# arpie2_display.net
KiCad netlist of a schematic drawn in EAGLE
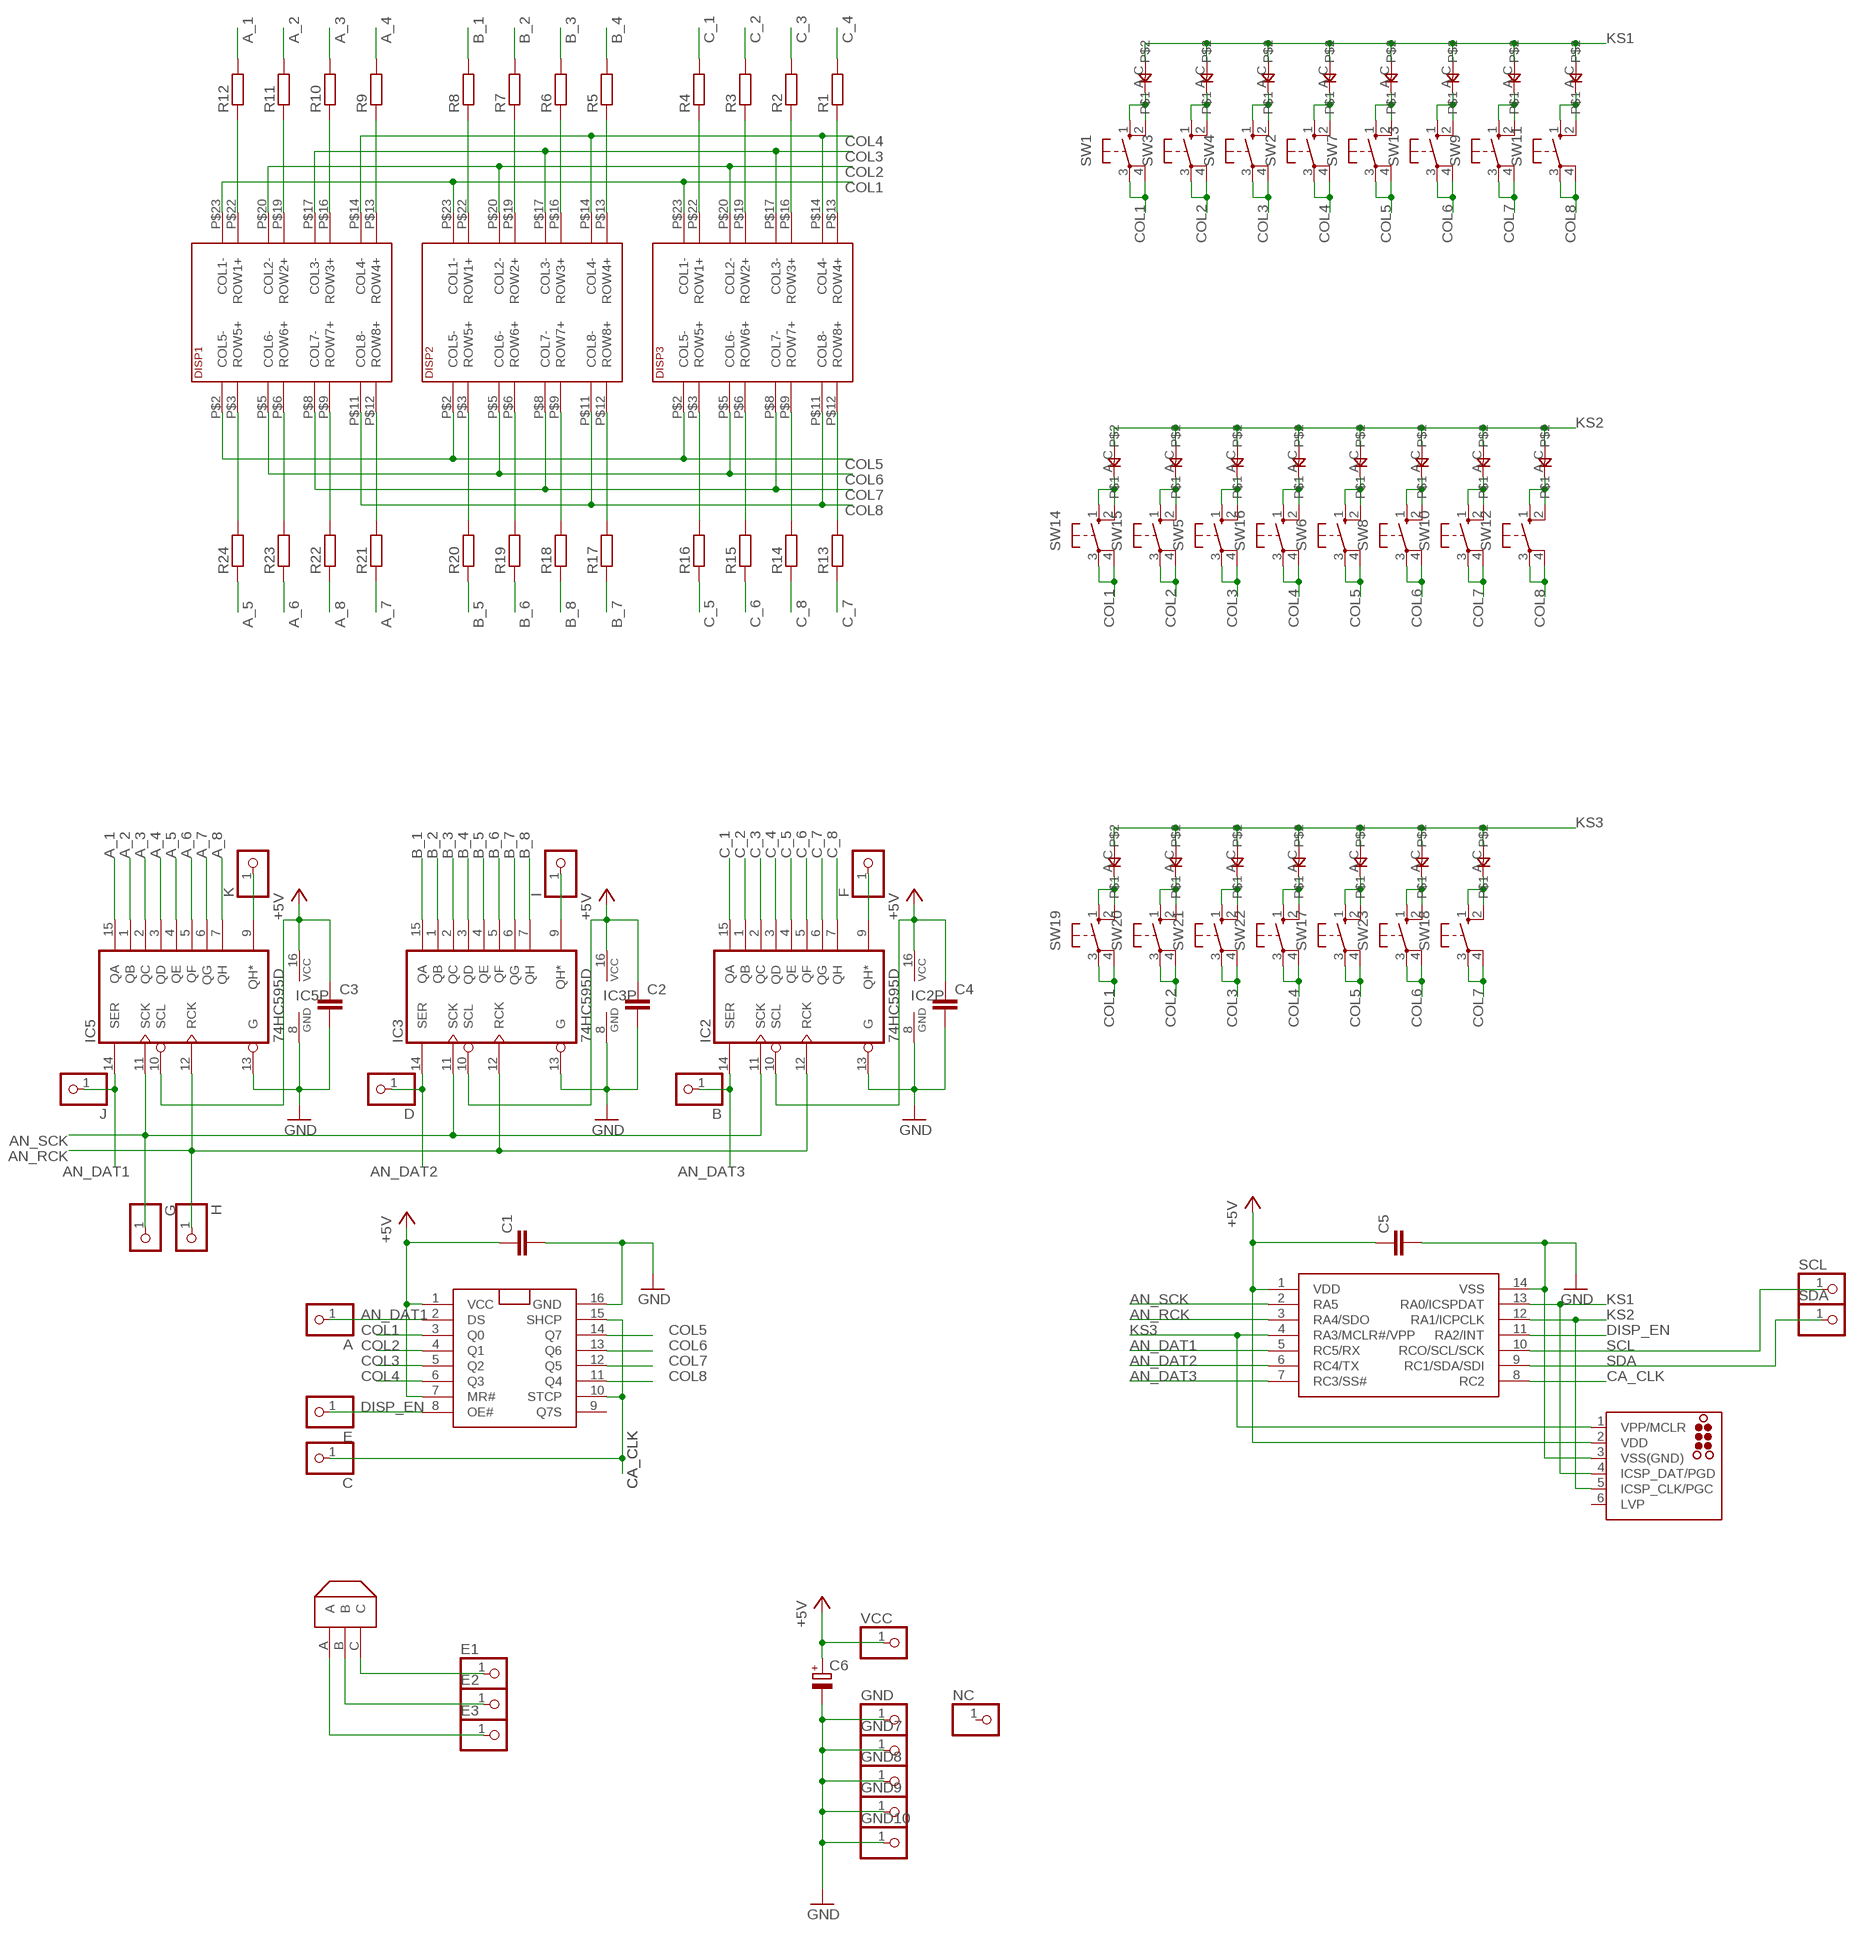
[diagram p0: schematic, sheet 1]

(export (version "E")
  (design (tool "Eeschema 10.0.6"))
  (components
    (comp (ref "A")
      (value "PINHD-1X1")
      (footprint "eagle-import:1X01")
      (libsource (lib "eagle-import") (part "PINHD-1X1"))
    )
    (comp (ref "B")
      (value "PINHD-1X1")
      (footprint "eagle-import:1X01")
      (libsource (lib "eagle-import") (part "PINHD-1X1"))
    )
    (comp (ref "C")
      (value "PINHD-1X1")
      (footprint "eagle-import:1X01")
      (libsource (lib "eagle-import") (part "PINHD-1X1"))
    )
    (comp (ref "C1")
      (value "C-EUC0805")
      (footprint "eagle-import:C0805")
      (libsource (lib "eagle-import") (part "C-EUC0805"))
    )
    (comp (ref "C2")
      (value "C-EUC0805")
      (footprint "eagle-import:C0805")
      (libsource (lib "eagle-import") (part "C-EUC0805"))
    )
    (comp (ref "C3")
      (value "C-EUC0805")
      (footprint "eagle-import:C0805")
      (libsource (lib "eagle-import") (part "C-EUC0805"))
    )
    (comp (ref "C4")
      (value "C-EUC0805")
      (footprint "eagle-import:C0805")
      (libsource (lib "eagle-import") (part "C-EUC0805"))
    )
    (comp (ref "C5")
      (value "C-EUC0805")
      (footprint "eagle-import:C0805")
      (libsource (lib "eagle-import") (part "C-EUC0805"))
    )
    (comp (ref "C6")
      (value "CPOL-EUE2,5-6E")
      (footprint "eagle-import:E2,5-6E")
      (libsource (lib "eagle-import") (part "CPOL-EUE2,5-6E"))
    )
    (comp (ref "D")
      (value "PINHD-1X1")
      (footprint "eagle-import:1X01")
      (libsource (lib "eagle-import") (part "PINHD-1X1"))
    )
    (comp (ref "DISP1")
      (value "1388BBMATRIX")
      (footprint "eagle-import:1388LEDMATRIX")
      (libsource (lib "eagle-import") (part "1388BBMATRIX"))
    )
    (comp (ref "DISP2")
      (value "1388BBMATRIX")
      (footprint "eagle-import:1388LEDMATRIX")
      (libsource (lib "eagle-import") (part "1388BBMATRIX"))
    )
    (comp (ref "DISP3")
      (value "1388BBMATRIX")
      (footprint "eagle-import:1388LEDMATRIX")
      (libsource (lib "eagle-import") (part "1388BBMATRIX"))
    )
    (comp (ref "E")
      (value "PINHD-1X1")
      (footprint "eagle-import:1X01")
      (libsource (lib "eagle-import") (part "PINHD-1X1"))
    )
    (comp (ref "E1")
      (value "PINHD-1X1")
      (footprint "eagle-import:1X01")
      (libsource (lib "eagle-import") (part "PINHD-1X1"))
    )
    (comp (ref "E2")
      (value "PINHD-1X1")
      (footprint "eagle-import:1X01")
      (libsource (lib "eagle-import") (part "PINHD-1X1"))
    )
    (comp (ref "E3")
      (value "PINHD-1X1")
      (footprint "eagle-import:1X01")
      (libsource (lib "eagle-import") (part "PINHD-1X1"))
    )
    (comp (ref "ENC1")
      (value "ENCODER")
      (footprint "eagle-import:ENCODER")
      (libsource (lib "eagle-import") (part "ENCODER"))
    )
    (comp (ref "F")
      (value "PINHD-1X1")
      (footprint "eagle-import:1X01")
      (libsource (lib "eagle-import") (part "PINHD-1X1"))
    )
    (comp (ref "G")
      (value "PINHD-1X1")
      (footprint "eagle-import:1X01")
      (libsource (lib "eagle-import") (part "PINHD-1X1"))
    )
    (comp (ref "GND")
      (value "PINHD-1X1")
      (footprint "eagle-import:1X01")
      (libsource (lib "eagle-import") (part "PINHD-1X1"))
    )
    (comp (ref "GND7")
      (value "PINHD-1X1")
      (footprint "eagle-import:1X01")
      (libsource (lib "eagle-import") (part "PINHD-1X1"))
    )
    (comp (ref "GND8")
      (value "PINHD-1X1")
      (footprint "eagle-import:1X01")
      (libsource (lib "eagle-import") (part "PINHD-1X1"))
    )
    (comp (ref "GND9")
      (value "PINHD-1X1")
      (footprint "eagle-import:1X01")
      (libsource (lib "eagle-import") (part "PINHD-1X1"))
    )
    (comp (ref "GND10")
      (value "PINHD-1X1")
      (footprint "eagle-import:1X01")
      (libsource (lib "eagle-import") (part "PINHD-1X1"))
    )
    (comp (ref "H")
      (value "PINHD-1X1")
      (footprint "eagle-import:1X01")
      (libsource (lib "eagle-import") (part "PINHD-1X1"))
    )
    (comp (ref "I")
      (value "PINHD-1X1")
      (footprint "eagle-import:1X01")
      (libsource (lib "eagle-import") (part "PINHD-1X1"))
    )
    (comp (ref "IC1")
      (value "PIC16F1825SO14")
      (footprint "eagle-import:SO14")
      (libsource (lib "eagle-import") (part "PIC16F1825SO14"))
    )
    (comp (ref "IC2")
      (value "74HC595D")
      (footprint "eagle-import:SO16")
      (libsource (lib "eagle-import") (part "74595DHC"))
    )
    (comp (ref "IC3")
      (value "74HC595D")
      (footprint "eagle-import:SO16")
      (libsource (lib "eagle-import") (part "74595DHC"))
    )
    (comp (ref "IC4")
      (value "NPIC6C596")
      (footprint "eagle-import:SO16")
      (libsource (lib "eagle-import") (part "NPIC6C596"))
    )
    (comp (ref "IC5")
      (value "74HC595D")
      (footprint "eagle-import:SO16")
      (libsource (lib "eagle-import") (part "74595DHC"))
    )
    (comp (ref "ICSP")
      (value "TC2030-MCP-NL")
      (footprint "eagle-import:TC2030-MCP-NL")
      (libsource (lib "eagle-import") (part "TC2030-MCP-NL"))
    )
    (comp (ref "J")
      (value "PINHD-1X1")
      (footprint "eagle-import:1X01")
      (libsource (lib "eagle-import") (part "PINHD-1X1"))
    )
    (comp (ref "K")
      (value "PINHD-1X1")
      (footprint "eagle-import:1X01")
      (libsource (lib "eagle-import") (part "PINHD-1X1"))
    )
    (comp (ref "NC")
      (value "PINHD-1X1")
      (footprint "eagle-import:1X01")
      (libsource (lib "eagle-import") (part "PINHD-1X1"))
    )
    (comp (ref "R1")
      (value "R-EU_R0805")
      (footprint "eagle-import:R0805")
      (libsource (lib "eagle-import") (part "R-EU_R0805"))
    )
    (comp (ref "R2")
      (value "R-EU_R0805")
      (footprint "eagle-import:R0805")
      (libsource (lib "eagle-import") (part "R-EU_R0805"))
    )
    (comp (ref "R3")
      (value "R-EU_R0805")
      (footprint "eagle-import:R0805")
      (libsource (lib "eagle-import") (part "R-EU_R0805"))
    )
    (comp (ref "R4")
      (value "R-EU_R0805")
      (footprint "eagle-import:R0805")
      (libsource (lib "eagle-import") (part "R-EU_R0805"))
    )
    (comp (ref "R5")
      (value "R-EU_R0805")
      (footprint "eagle-import:R0805")
      (libsource (lib "eagle-import") (part "R-EU_R0805"))
    )
    (comp (ref "R6")
      (value "R-EU_R0805")
      (footprint "eagle-import:R0805")
      (libsource (lib "eagle-import") (part "R-EU_R0805"))
    )
    (comp (ref "R7")
      (value "R-EU_R0805")
      (footprint "eagle-import:R0805")
      (libsource (lib "eagle-import") (part "R-EU_R0805"))
    )
    (comp (ref "R8")
      (value "R-EU_R0805")
      (footprint "eagle-import:R0805")
      (libsource (lib "eagle-import") (part "R-EU_R0805"))
    )
    (comp (ref "R9")
      (value "R-EU_R0805")
      (footprint "eagle-import:R0805")
      (libsource (lib "eagle-import") (part "R-EU_R0805"))
    )
    (comp (ref "R10")
      (value "R-EU_R0805")
      (footprint "eagle-import:R0805")
      (libsource (lib "eagle-import") (part "R-EU_R0805"))
    )
    (comp (ref "R11")
      (value "R-EU_R0805")
      (footprint "eagle-import:R0805")
      (libsource (lib "eagle-import") (part "R-EU_R0805"))
    )
    (comp (ref "R12")
      (value "R-EU_R0805")
      (footprint "eagle-import:R0805")
      (libsource (lib "eagle-import") (part "R-EU_R0805"))
    )
    (comp (ref "R13")
      (value "R-EU_R0805")
      (footprint "eagle-import:R0805")
      (libsource (lib "eagle-import") (part "R-EU_R0805"))
    )
    (comp (ref "R14")
      (value "R-EU_R0805")
      (footprint "eagle-import:R0805")
      (libsource (lib "eagle-import") (part "R-EU_R0805"))
    )
    (comp (ref "R15")
      (value "R-EU_R0805")
      (footprint "eagle-import:R0805")
      (libsource (lib "eagle-import") (part "R-EU_R0805"))
    )
    (comp (ref "R16")
      (value "R-EU_R0805")
      (footprint "eagle-import:R0805")
      (libsource (lib "eagle-import") (part "R-EU_R0805"))
    )
    (comp (ref "R17")
      (value "R-EU_R0805")
      (footprint "eagle-import:R0805")
      (libsource (lib "eagle-import") (part "R-EU_R0805"))
    )
    (comp (ref "R18")
      (value "R-EU_R0805")
      (footprint "eagle-import:R0805")
      (libsource (lib "eagle-import") (part "R-EU_R0805"))
    )
    (comp (ref "R19")
      (value "R-EU_R0805")
      (footprint "eagle-import:R0805")
      (libsource (lib "eagle-import") (part "R-EU_R0805"))
    )
    (comp (ref "R20")
      (value "R-EU_R0805")
      (footprint "eagle-import:R0805")
      (libsource (lib "eagle-import") (part "R-EU_R0805"))
    )
    (comp (ref "R21")
      (value "R-EU_R0805")
      (footprint "eagle-import:R0805")
      (libsource (lib "eagle-import") (part "R-EU_R0805"))
    )
    (comp (ref "R22")
      (value "R-EU_R0805")
      (footprint "eagle-import:R0805")
      (libsource (lib "eagle-import") (part "R-EU_R0805"))
    )
    (comp (ref "R23")
      (value "R-EU_R0805")
      (footprint "eagle-import:R0805")
      (libsource (lib "eagle-import") (part "R-EU_R0805"))
    )
    (comp (ref "R24")
      (value "R-EU_R0805")
      (footprint "eagle-import:R0805")
      (libsource (lib "eagle-import") (part "R-EU_R0805"))
    )
    (comp (ref "SCL")
      (value "PINHD-1X1")
      (footprint "eagle-import:1X01")
      (libsource (lib "eagle-import") (part "PINHD-1X1"))
    )
    (comp (ref "SDA")
      (value "PINHD-1X1")
      (footprint "eagle-import:1X01")
      (libsource (lib "eagle-import") (part "PINHD-1X1"))
    )
    (comp (ref "SW1")
      (value "10-XX")
      (footprint "eagle-import:B3F-10XX")
      (fields (field (name "MPN") "B3F-1000"))
      (libsource (lib "eagle-import") (part "10-XX"))
    )
    (comp (ref "SW2")
      (value "10-XX")
      (footprint "eagle-import:B3F-10XX")
      (fields (field (name "MPN") "B3F-1000"))
      (libsource (lib "eagle-import") (part "10-XX"))
    )
    (comp (ref "SW3")
      (value "10-XX")
      (footprint "eagle-import:B3F-10XX")
      (fields (field (name "MPN") "B3F-1000"))
      (libsource (lib "eagle-import") (part "10-XX"))
    )
    (comp (ref "SW4")
      (value "10-XX")
      (footprint "eagle-import:B3F-10XX")
      (fields (field (name "MPN") "B3F-1000"))
      (libsource (lib "eagle-import") (part "10-XX"))
    )
    (comp (ref "SW5")
      (value "10-XX")
      (footprint "eagle-import:B3F-10XX")
      (fields (field (name "MPN") "B3F-1000"))
      (libsource (lib "eagle-import") (part "10-XX"))
    )
    (comp (ref "SW6")
      (value "10-XX")
      (footprint "eagle-import:B3F-10XX")
      (fields (field (name "MPN") "B3F-1000"))
      (libsource (lib "eagle-import") (part "10-XX"))
    )
    (comp (ref "SW7")
      (value "10-XX")
      (footprint "eagle-import:B3F-10XX")
      (fields (field (name "MPN") "B3F-1000"))
      (libsource (lib "eagle-import") (part "10-XX"))
    )
    (comp (ref "SW8")
      (value "10-XX")
      (footprint "eagle-import:B3F-10XX")
      (fields (field (name "MPN") "B3F-1000"))
      (libsource (lib "eagle-import") (part "10-XX"))
    )
    (comp (ref "SW9")
      (value "10-XX")
      (footprint "eagle-import:B3F-10XX")
      (fields (field (name "MPN") "B3F-1000"))
      (libsource (lib "eagle-import") (part "10-XX"))
    )
    (comp (ref "SW10")
      (value "10-XX")
      (footprint "eagle-import:B3F-10XX")
      (fields (field (name "MPN") "B3F-1000"))
      (libsource (lib "eagle-import") (part "10-XX"))
    )
    (comp (ref "SW11")
      (value "10-XX")
      (footprint "eagle-import:B3F-10XX")
      (fields (field (name "MPN") "B3F-1000"))
      (libsource (lib "eagle-import") (part "10-XX"))
    )
    (comp (ref "SW12")
      (value "10-XX")
      (footprint "eagle-import:B3F-10XX")
      (fields (field (name "MPN") "B3F-1000"))
      (libsource (lib "eagle-import") (part "10-XX"))
    )
    (comp (ref "SW13")
      (value "10-XX")
      (footprint "eagle-import:B3F-10XX")
      (fields (field (name "MPN") "B3F-1000"))
      (libsource (lib "eagle-import") (part "10-XX"))
    )
    (comp (ref "SW14")
      (value "10-XX")
      (footprint "eagle-import:B3F-10XX")
      (fields (field (name "MPN") "B3F-1000"))
      (libsource (lib "eagle-import") (part "10-XX"))
    )
    (comp (ref "SW15")
      (value "10-XX")
      (footprint "eagle-import:B3F-10XX")
      (fields (field (name "MPN") "B3F-1000"))
      (libsource (lib "eagle-import") (part "10-XX"))
    )
    (comp (ref "SW16")
      (value "10-XX")
      (footprint "eagle-import:B3F-10XX")
      (fields (field (name "MPN") "B3F-1000"))
      (libsource (lib "eagle-import") (part "10-XX"))
    )
    (comp (ref "SW17")
      (value "10-XX")
      (footprint "eagle-import:B3F-10XX")
      (fields (field (name "MPN") "B3F-1000"))
      (libsource (lib "eagle-import") (part "10-XX"))
    )
    (comp (ref "SW18")
      (value "10-XX")
      (footprint "eagle-import:B3F-10XX")
      (fields (field (name "MPN") "B3F-1000"))
      (libsource (lib "eagle-import") (part "10-XX"))
    )
    (comp (ref "SW19")
      (value "10-XX")
      (footprint "eagle-import:B3F-10XX")
      (fields (field (name "MPN") "B3F-1000"))
      (libsource (lib "eagle-import") (part "10-XX"))
    )
    (comp (ref "SW20")
      (value "10-XX")
      (footprint "eagle-import:B3F-10XX")
      (fields (field (name "MPN") "B3F-1000"))
      (libsource (lib "eagle-import") (part "10-XX"))
    )
    (comp (ref "SW21")
      (value "10-XX")
      (footprint "eagle-import:B3F-10XX")
      (fields (field (name "MPN") "B3F-1000"))
      (libsource (lib "eagle-import") (part "10-XX"))
    )
    (comp (ref "SW22")
      (value "10-XX")
      (footprint "eagle-import:B3F-10XX")
      (fields (field (name "MPN") "B3F-1000"))
      (libsource (lib "eagle-import") (part "10-XX"))
    )
    (comp (ref "SW23")
      (value "10-XX")
      (footprint "eagle-import:B3F-10XX")
      (fields (field (name "MPN") "B3F-1000"))
      (libsource (lib "eagle-import") (part "10-XX"))
    )
    (comp (ref "U$2")
      (value "0805DIODE")
      (footprint "eagle-import:0805DIODE")
      (libsource (lib "eagle-import") (part "0805DIODE"))
    )
    (comp (ref "U$3")
      (value "0805DIODE")
      (footprint "eagle-import:0805DIODE")
      (libsource (lib "eagle-import") (part "0805DIODE"))
    )
    (comp (ref "U$4")
      (value "0805DIODE")
      (footprint "eagle-import:0805DIODE")
      (libsource (lib "eagle-import") (part "0805DIODE"))
    )
    (comp (ref "U$5")
      (value "0805DIODE")
      (footprint "eagle-import:0805DIODE")
      (libsource (lib "eagle-import") (part "0805DIODE"))
    )
    (comp (ref "U$6")
      (value "0805DIODE")
      (footprint "eagle-import:0805DIODE")
      (libsource (lib "eagle-import") (part "0805DIODE"))
    )
    (comp (ref "U$7")
      (value "0805DIODE")
      (footprint "eagle-import:0805DIODE")
      (libsource (lib "eagle-import") (part "0805DIODE"))
    )
    (comp (ref "U$8")
      (value "0805DIODE")
      (footprint "eagle-import:0805DIODE")
      (libsource (lib "eagle-import") (part "0805DIODE"))
    )
    (comp (ref "U$9")
      (value "0805DIODE")
      (footprint "eagle-import:0805DIODE")
      (libsource (lib "eagle-import") (part "0805DIODE"))
    )
    (comp (ref "U$10")
      (value "0805DIODE")
      (footprint "eagle-import:0805DIODE")
      (libsource (lib "eagle-import") (part "0805DIODE"))
    )
    (comp (ref "U$11")
      (value "0805DIODE")
      (footprint "eagle-import:0805DIODE")
      (libsource (lib "eagle-import") (part "0805DIODE"))
    )
    (comp (ref "U$12")
      (value "0805DIODE")
      (footprint "eagle-import:0805DIODE")
      (libsource (lib "eagle-import") (part "0805DIODE"))
    )
    (comp (ref "U$13")
      (value "0805DIODE")
      (footprint "eagle-import:0805DIODE")
      (libsource (lib "eagle-import") (part "0805DIODE"))
    )
    (comp (ref "U$14")
      (value "0805DIODE")
      (footprint "eagle-import:0805DIODE")
      (libsource (lib "eagle-import") (part "0805DIODE"))
    )
    (comp (ref "U$15")
      (value "0805DIODE")
      (footprint "eagle-import:0805DIODE")
      (libsource (lib "eagle-import") (part "0805DIODE"))
    )
    (comp (ref "U$16")
      (value "0805DIODE")
      (footprint "eagle-import:0805DIODE")
      (libsource (lib "eagle-import") (part "0805DIODE"))
    )
    (comp (ref "U$17")
      (value "0805DIODE")
      (footprint "eagle-import:0805DIODE")
      (libsource (lib "eagle-import") (part "0805DIODE"))
    )
    (comp (ref "U$18")
      (value "0805DIODE")
      (footprint "eagle-import:0805DIODE")
      (libsource (lib "eagle-import") (part "0805DIODE"))
    )
    (comp (ref "U$19")
      (value "0805DIODE")
      (footprint "eagle-import:0805DIODE")
      (libsource (lib "eagle-import") (part "0805DIODE"))
    )
    (comp (ref "U$20")
      (value "0805DIODE")
      (footprint "eagle-import:0805DIODE")
      (libsource (lib "eagle-import") (part "0805DIODE"))
    )
    (comp (ref "U$21")
      (value "0805DIODE")
      (footprint "eagle-import:0805DIODE")
      (libsource (lib "eagle-import") (part "0805DIODE"))
    )
    (comp (ref "U$22")
      (value "0805DIODE")
      (footprint "eagle-import:0805DIODE")
      (libsource (lib "eagle-import") (part "0805DIODE"))
    )
    (comp (ref "U$23")
      (value "0805DIODE")
      (footprint "eagle-import:0805DIODE")
      (libsource (lib "eagle-import") (part "0805DIODE"))
    )
    (comp (ref "U$24")
      (value "0805DIODE")
      (footprint "eagle-import:0805DIODE")
      (libsource (lib "eagle-import") (part "0805DIODE"))
    )
    (comp (ref "VCC")
      (value "PINHD-1X1")
      (footprint "eagle-import:1X01")
      (libsource (lib "eagle-import") (part "PINHD-1X1"))
    )
  )
  (nets
    (net (code "1") (name "+5V") (class "Default")
      (node (ref "C1") (pin "1") (pinfunction "1_1") (pintype "passive"))
      (node (ref "C2") (pin "1") (pinfunction "1_1") (pintype "passive"))
      (node (ref "C3") (pin "1") (pinfunction "1_1") (pintype "passive"))
      (node (ref "C4") (pin "1") (pinfunction "1_1") (pintype "passive"))
      (node (ref "C5") (pin "1") (pinfunction "1_1") (pintype "passive"))
      (node (ref "C6") (pin "+") (pinfunction "+_+") (pintype "passive"))
      (node (ref "IC1") (pin "1") (pinfunction "VDD_1") (pintype "power_in"))
      (node (ref "IC2") (pin "10") (pinfunction "SCL_10") (pintype "input"))
      (node (ref "IC2") (pin "16") (pinfunction "VCC_16") (pintype "power_in"))
      (node (ref "IC3") (pin "10") (pinfunction "SCL_10") (pintype "input"))
      (node (ref "IC3") (pin "16") (pinfunction "VCC_16") (pintype "power_in"))
      (node (ref "IC4") (pin "1") (pinfunction "VCC_1") (pintype "power_in"))
      (node (ref "IC4") (pin "7") (pinfunction "MR#_7") (pintype "input"))
      (node (ref "IC5") (pin "10") (pinfunction "SCL_10") (pintype "input"))
      (node (ref "IC5") (pin "16") (pinfunction "VCC_16") (pintype "power_in"))
      (node (ref "ICSP") (pin "2") (pinfunction "VDD_2") (pintype "power_in"))
      (node (ref "VCC") (pin "1") (pinfunction "1_1") (pintype "passive"))
    )
    (net (code "2") (name "/AN_DAT1") (class "Default")
      (node (ref "A") (pin "1") (pinfunction "1_1") (pintype "passive"))
      (node (ref "IC1") (pin "5") (pinfunction "RC5/RX_5") (pintype "bidirectional"))
      (node (ref "IC4") (pin "2") (pinfunction "DS_2") (pintype "input"))
      (node (ref "IC5") (pin "14") (pinfunction "SER_14") (pintype "input"))
      (node (ref "J") (pin "1") (pinfunction "1_1") (pintype "passive"))
    )
    (net (code "3") (name "/AN_DAT2") (class "Default")
      (node (ref "D") (pin "1") (pinfunction "1_1") (pintype "passive"))
      (node (ref "IC1") (pin "6") (pinfunction "RC4/TX_6") (pintype "bidirectional"))
      (node (ref "IC3") (pin "14") (pinfunction "SER_14") (pintype "input"))
    )
    (net (code "4") (name "/AN_DAT3") (class "Default")
      (node (ref "B") (pin "1") (pinfunction "1_1") (pintype "passive"))
      (node (ref "IC1") (pin "7") (pinfunction "RC3/SS#_7") (pintype "bidirectional"))
      (node (ref "IC2") (pin "14") (pinfunction "SER_14") (pintype "input"))
    )
    (net (code "5") (name "/AN_RCK") (class "Default")
      (node (ref "H") (pin "1") (pinfunction "1_1") (pintype "passive"))
      (node (ref "IC1") (pin "3") (pinfunction "RA4/SDO_3") (pintype "bidirectional"))
      (node (ref "IC2") (pin "12") (pinfunction "RCK_12") (pintype "input"))
      (node (ref "IC3") (pin "12") (pinfunction "RCK_12") (pintype "input"))
      (node (ref "IC5") (pin "12") (pinfunction "RCK_12") (pintype "input"))
    )
    (net (code "6") (name "/AN_SCK") (class "Default")
      (node (ref "G") (pin "1") (pinfunction "1_1") (pintype "passive"))
      (node (ref "IC1") (pin "2") (pinfunction "RA5_2") (pintype "bidirectional"))
      (node (ref "IC2") (pin "11") (pinfunction "SCK_11") (pintype "input"))
      (node (ref "IC3") (pin "11") (pinfunction "SCK_11") (pintype "input"))
      (node (ref "IC5") (pin "11") (pinfunction "SCK_11") (pintype "input"))
    )
    (net (code "7") (name "/A_1") (class "Default")
      (node (ref "IC5") (pin "15") (pinfunction "QA_15") (pintype "tri_state"))
      (node (ref "R12") (pin "2") (pinfunction "2_2") (pintype "passive"))
    )
    (net (code "8") (name "/A_2") (class "Default")
      (node (ref "IC5") (pin "1") (pinfunction "QB_1") (pintype "tri_state"))
      (node (ref "R11") (pin "2") (pinfunction "2_2") (pintype "passive"))
    )
    (net (code "9") (name "/A_3") (class "Default")
      (node (ref "IC5") (pin "2") (pinfunction "QC_2") (pintype "tri_state"))
      (node (ref "R10") (pin "2") (pinfunction "2_2") (pintype "passive"))
    )
    (net (code "10") (name "/A_4") (class "Default")
      (node (ref "IC5") (pin "3") (pinfunction "QD_3") (pintype "tri_state"))
      (node (ref "R9") (pin "2") (pinfunction "2_2") (pintype "passive"))
    )
    (net (code "11") (name "/A_5") (class "Default")
      (node (ref "IC5") (pin "4") (pinfunction "QE_4") (pintype "tri_state"))
      (node (ref "R24") (pin "1") (pinfunction "1_1") (pintype "passive"))
    )
    (net (code "12") (name "/A_6") (class "Default")
      (node (ref "IC5") (pin "5") (pinfunction "QF_5") (pintype "tri_state"))
      (node (ref "R23") (pin "1") (pinfunction "1_1") (pintype "passive"))
    )
    (net (code "13") (name "/A_7") (class "Default")
      (node (ref "IC5") (pin "6") (pinfunction "QG_6") (pintype "tri_state"))
      (node (ref "R21") (pin "1") (pinfunction "1_1") (pintype "passive"))
    )
    (net (code "14") (name "/A_8") (class "Default")
      (node (ref "IC5") (pin "7") (pinfunction "QH_7") (pintype "tri_state"))
      (node (ref "R22") (pin "1") (pinfunction "1_1") (pintype "passive"))
    )
    (net (code "15") (name "/B_1") (class "Default")
      (node (ref "IC3") (pin "15") (pinfunction "QA_15") (pintype "tri_state"))
      (node (ref "R8") (pin "2") (pinfunction "2_2") (pintype "passive"))
    )
    (net (code "16") (name "/B_2") (class "Default")
      (node (ref "IC3") (pin "1") (pinfunction "QB_1") (pintype "tri_state"))
      (node (ref "R7") (pin "2") (pinfunction "2_2") (pintype "passive"))
    )
    (net (code "17") (name "/B_3") (class "Default")
      (node (ref "IC3") (pin "2") (pinfunction "QC_2") (pintype "tri_state"))
      (node (ref "R6") (pin "2") (pinfunction "2_2") (pintype "passive"))
    )
    (net (code "18") (name "/B_4") (class "Default")
      (node (ref "IC3") (pin "3") (pinfunction "QD_3") (pintype "tri_state"))
      (node (ref "R5") (pin "2") (pinfunction "2_2") (pintype "passive"))
    )
    (net (code "19") (name "/B_5") (class "Default")
      (node (ref "IC3") (pin "4") (pinfunction "QE_4") (pintype "tri_state"))
      (node (ref "R20") (pin "1") (pinfunction "1_1") (pintype "passive"))
    )
    (net (code "20") (name "/B_6") (class "Default")
      (node (ref "IC3") (pin "5") (pinfunction "QF_5") (pintype "tri_state"))
      (node (ref "R19") (pin "1") (pinfunction "1_1") (pintype "passive"))
    )
    (net (code "21") (name "/B_7") (class "Default")
      (node (ref "IC3") (pin "6") (pinfunction "QG_6") (pintype "tri_state"))
      (node (ref "R17") (pin "1") (pinfunction "1_1") (pintype "passive"))
    )
    (net (code "22") (name "/B_8") (class "Default")
      (node (ref "IC3") (pin "7") (pinfunction "QH_7") (pintype "tri_state"))
      (node (ref "R18") (pin "1") (pinfunction "1_1") (pintype "passive"))
    )
    (net (code "23") (name "/CA_CLK") (class "Default")
      (node (ref "C") (pin "1") (pinfunction "1_1") (pintype "passive"))
      (node (ref "IC1") (pin "8") (pinfunction "RC2_8") (pintype "bidirectional"))
      (node (ref "IC4") (pin "10") (pinfunction "STCP_10") (pintype "input"))
      (node (ref "IC4") (pin "15") (pinfunction "SHCP_15") (pintype "input"))
    )
    (net (code "24") (name "/COL1") (class "Default")
      (node (ref "DISP1") (pin "P$23") (pinfunction "COL1-_P$23") (pintype "bidirectional"))
      (node (ref "DISP2") (pin "P$23") (pinfunction "COL1-_P$23") (pintype "bidirectional"))
      (node (ref "DISP3") (pin "P$23") (pinfunction "COL1-_P$23") (pintype "bidirectional"))
      (node (ref "IC4") (pin "3") (pinfunction "Q0_3") (pintype "open_collector"))
      (node (ref "SW1") (pin "3") (pinfunction "P_3") (pintype "passive"))
      (node (ref "SW1") (pin "4") (pinfunction "P1_4") (pintype "passive"))
      (node (ref "SW14") (pin "3") (pinfunction "P_3") (pintype "passive"))
      (node (ref "SW14") (pin "4") (pinfunction "P1_4") (pintype "passive"))
      (node (ref "SW19") (pin "3") (pinfunction "P_3") (pintype "passive"))
      (node (ref "SW19") (pin "4") (pinfunction "P1_4") (pintype "passive"))
    )
    (net (code "25") (name "/COL2") (class "Default")
      (node (ref "DISP1") (pin "P$20") (pinfunction "COL2-_P$20") (pintype "bidirectional"))
      (node (ref "DISP2") (pin "P$20") (pinfunction "COL2-_P$20") (pintype "bidirectional"))
      (node (ref "DISP3") (pin "P$20") (pinfunction "COL2-_P$20") (pintype "bidirectional"))
      (node (ref "IC4") (pin "4") (pinfunction "Q1_4") (pintype "open_collector"))
      (node (ref "SW15") (pin "3") (pinfunction "P_3") (pintype "passive"))
      (node (ref "SW15") (pin "4") (pinfunction "P1_4") (pintype "passive"))
      (node (ref "SW20") (pin "3") (pinfunction "P_3") (pintype "passive"))
      (node (ref "SW20") (pin "4") (pinfunction "P1_4") (pintype "passive"))
      (node (ref "SW3") (pin "3") (pinfunction "P_3") (pintype "passive"))
      (node (ref "SW3") (pin "4") (pinfunction "P1_4") (pintype "passive"))
    )
    (net (code "26") (name "/COL3") (class "Default")
      (node (ref "DISP1") (pin "P$17") (pinfunction "COL3-_P$17") (pintype "bidirectional"))
      (node (ref "DISP2") (pin "P$17") (pinfunction "COL3-_P$17") (pintype "bidirectional"))
      (node (ref "DISP3") (pin "P$17") (pinfunction "COL3-_P$17") (pintype "bidirectional"))
      (node (ref "IC4") (pin "5") (pinfunction "Q2_5") (pintype "open_collector"))
      (node (ref "SW21") (pin "3") (pinfunction "P_3") (pintype "passive"))
      (node (ref "SW21") (pin "4") (pinfunction "P1_4") (pintype "passive"))
      (node (ref "SW4") (pin "3") (pinfunction "P_3") (pintype "passive"))
      (node (ref "SW4") (pin "4") (pinfunction "P1_4") (pintype "passive"))
      (node (ref "SW5") (pin "3") (pinfunction "P_3") (pintype "passive"))
      (node (ref "SW5") (pin "4") (pinfunction "P1_4") (pintype "passive"))
    )
    (net (code "27") (name "/COL4") (class "Default")
      (node (ref "DISP1") (pin "P$14") (pinfunction "COL4-_P$14") (pintype "bidirectional"))
      (node (ref "DISP2") (pin "P$14") (pinfunction "COL4-_P$14") (pintype "bidirectional"))
      (node (ref "DISP3") (pin "P$14") (pinfunction "COL4-_P$14") (pintype "bidirectional"))
      (node (ref "IC4") (pin "6") (pinfunction "Q3_6") (pintype "open_collector"))
      (node (ref "SW16") (pin "3") (pinfunction "P_3") (pintype "passive"))
      (node (ref "SW16") (pin "4") (pinfunction "P1_4") (pintype "passive"))
      (node (ref "SW2") (pin "3") (pinfunction "P_3") (pintype "passive"))
      (node (ref "SW2") (pin "4") (pinfunction "P1_4") (pintype "passive"))
      (node (ref "SW22") (pin "3") (pinfunction "P_3") (pintype "passive"))
      (node (ref "SW22") (pin "4") (pinfunction "P1_4") (pintype "passive"))
    )
    (net (code "28") (name "/COL5") (class "Default")
      (node (ref "DISP1") (pin "P$2") (pinfunction "COL5-_P$2") (pintype "bidirectional"))
      (node (ref "DISP2") (pin "P$2") (pinfunction "COL5-_P$2") (pintype "bidirectional"))
      (node (ref "DISP3") (pin "P$2") (pinfunction "COL5-_P$2") (pintype "bidirectional"))
      (node (ref "IC4") (pin "14") (pinfunction "Q7_14") (pintype "open_collector"))
      (node (ref "SW17") (pin "3") (pinfunction "P_3") (pintype "passive"))
      (node (ref "SW17") (pin "4") (pinfunction "P1_4") (pintype "passive"))
      (node (ref "SW6") (pin "3") (pinfunction "P_3") (pintype "passive"))
      (node (ref "SW6") (pin "4") (pinfunction "P1_4") (pintype "passive"))
      (node (ref "SW7") (pin "3") (pinfunction "P_3") (pintype "passive"))
      (node (ref "SW7") (pin "4") (pinfunction "P1_4") (pintype "passive"))
    )
    (net (code "29") (name "/COL6") (class "Default")
      (node (ref "DISP1") (pin "P$5") (pinfunction "COL6-_P$5") (pintype "bidirectional"))
      (node (ref "DISP2") (pin "P$5") (pinfunction "COL6-_P$5") (pintype "bidirectional"))
      (node (ref "DISP3") (pin "P$5") (pinfunction "COL6-_P$5") (pintype "bidirectional"))
      (node (ref "IC4") (pin "13") (pinfunction "Q6_13") (pintype "open_collector"))
      (node (ref "SW13") (pin "3") (pinfunction "P_3") (pintype "passive"))
      (node (ref "SW13") (pin "4") (pinfunction "P1_4") (pintype "passive"))
      (node (ref "SW23") (pin "3") (pinfunction "P_3") (pintype "passive"))
      (node (ref "SW23") (pin "4") (pinfunction "P1_4") (pintype "passive"))
      (node (ref "SW8") (pin "3") (pinfunction "P_3") (pintype "passive"))
      (node (ref "SW8") (pin "4") (pinfunction "P1_4") (pintype "passive"))
    )
    (net (code "30") (name "/COL7") (class "Default")
      (node (ref "DISP1") (pin "P$8") (pinfunction "COL7-_P$8") (pintype "bidirectional"))
      (node (ref "DISP2") (pin "P$8") (pinfunction "COL7-_P$8") (pintype "bidirectional"))
      (node (ref "DISP3") (pin "P$8") (pinfunction "COL7-_P$8") (pintype "bidirectional"))
      (node (ref "IC4") (pin "12") (pinfunction "Q5_12") (pintype "open_collector"))
      (node (ref "SW10") (pin "3") (pinfunction "P_3") (pintype "passive"))
      (node (ref "SW10") (pin "4") (pinfunction "P1_4") (pintype "passive"))
      (node (ref "SW18") (pin "3") (pinfunction "P_3") (pintype "passive"))
      (node (ref "SW18") (pin "4") (pinfunction "P1_4") (pintype "passive"))
      (node (ref "SW9") (pin "3") (pinfunction "P_3") (pintype "passive"))
      (node (ref "SW9") (pin "4") (pinfunction "P1_4") (pintype "passive"))
    )
    (net (code "31") (name "/COL8") (class "Default")
      (node (ref "DISP1") (pin "P$11") (pinfunction "COL8-_P$11") (pintype "bidirectional"))
      (node (ref "DISP2") (pin "P$11") (pinfunction "COL8-_P$11") (pintype "bidirectional"))
      (node (ref "DISP3") (pin "P$11") (pinfunction "COL8-_P$11") (pintype "bidirectional"))
      (node (ref "IC4") (pin "11") (pinfunction "Q4_11") (pintype "open_collector"))
      (node (ref "SW11") (pin "3") (pinfunction "P_3") (pintype "passive"))
      (node (ref "SW11") (pin "4") (pinfunction "P1_4") (pintype "passive"))
      (node (ref "SW12") (pin "3") (pinfunction "P_3") (pintype "passive"))
      (node (ref "SW12") (pin "4") (pinfunction "P1_4") (pintype "passive"))
    )
    (net (code "32") (name "/C_1") (class "Default")
      (node (ref "IC2") (pin "15") (pinfunction "QA_15") (pintype "tri_state"))
      (node (ref "R4") (pin "2") (pinfunction "2_2") (pintype "passive"))
    )
    (net (code "33") (name "/C_2") (class "Default")
      (node (ref "IC2") (pin "1") (pinfunction "QB_1") (pintype "tri_state"))
      (node (ref "R3") (pin "2") (pinfunction "2_2") (pintype "passive"))
    )
    (net (code "34") (name "/C_3") (class "Default")
      (node (ref "IC2") (pin "2") (pinfunction "QC_2") (pintype "tri_state"))
      (node (ref "R2") (pin "2") (pinfunction "2_2") (pintype "passive"))
    )
    (net (code "35") (name "/C_4") (class "Default")
      (node (ref "IC2") (pin "3") (pinfunction "QD_3") (pintype "tri_state"))
      (node (ref "R1") (pin "2") (pinfunction "2_2") (pintype "passive"))
    )
    (net (code "36") (name "/C_5") (class "Default")
      (node (ref "IC2") (pin "4") (pinfunction "QE_4") (pintype "tri_state"))
      (node (ref "R16") (pin "1") (pinfunction "1_1") (pintype "passive"))
    )
    (net (code "37") (name "/C_6") (class "Default")
      (node (ref "IC2") (pin "5") (pinfunction "QF_5") (pintype "tri_state"))
      (node (ref "R15") (pin "1") (pinfunction "1_1") (pintype "passive"))
    )
    (net (code "38") (name "/C_7") (class "Default")
      (node (ref "IC2") (pin "6") (pinfunction "QG_6") (pintype "tri_state"))
      (node (ref "R13") (pin "1") (pinfunction "1_1") (pintype "passive"))
    )
    (net (code "39") (name "/C_8") (class "Default")
      (node (ref "IC2") (pin "7") (pinfunction "QH_7") (pintype "tri_state"))
      (node (ref "R14") (pin "1") (pinfunction "1_1") (pintype "passive"))
    )
    (net (code "40") (name "/DISP_EN") (class "Default")
      (node (ref "E") (pin "1") (pinfunction "1_1") (pintype "passive"))
      (node (ref "IC1") (pin "11") (pinfunction "RA2/INT_11") (pintype "bidirectional"))
      (node (ref "IC4") (pin "8") (pinfunction "OE#_8") (pintype "input"))
    )
    (net (code "41") (name "/KS1") (class "Default")
      (node (ref "IC1") (pin "13") (pinfunction "RA0/ICSPDAT_13") (pintype "bidirectional"))
      (node (ref "ICSP") (pin "4") (pinfunction "ICSP_DAT/PGD_4") (pintype "bidirectional"))
      (node (ref "U$2") (pin "C") (pinfunction "P$1_C") (pintype "bidirectional"))
      (node (ref "U$3") (pin "C") (pinfunction "P$1_C") (pintype "bidirectional"))
      (node (ref "U$4") (pin "C") (pinfunction "P$1_C") (pintype "bidirectional"))
      (node (ref "U$5") (pin "C") (pinfunction "P$1_C") (pintype "bidirectional"))
      (node (ref "U$6") (pin "C") (pinfunction "P$1_C") (pintype "bidirectional"))
      (node (ref "U$7") (pin "C") (pinfunction "P$1_C") (pintype "bidirectional"))
      (node (ref "U$8") (pin "C") (pinfunction "P$1_C") (pintype "bidirectional"))
      (node (ref "U$9") (pin "C") (pinfunction "P$1_C") (pintype "bidirectional"))
    )
    (net (code "42") (name "/KS2") (class "Default")
      (node (ref "IC1") (pin "12") (pinfunction "RA1/ICPCLK_12") (pintype "bidirectional"))
      (node (ref "ICSP") (pin "5") (pinfunction "ICSP_CLK/PGC_5") (pintype "output"))
      (node (ref "U$10") (pin "C") (pinfunction "P$1_C") (pintype "bidirectional"))
      (node (ref "U$11") (pin "C") (pinfunction "P$1_C") (pintype "bidirectional"))
      (node (ref "U$12") (pin "C") (pinfunction "P$1_C") (pintype "bidirectional"))
      (node (ref "U$13") (pin "C") (pinfunction "P$1_C") (pintype "bidirectional"))
      (node (ref "U$14") (pin "C") (pinfunction "P$1_C") (pintype "bidirectional"))
      (node (ref "U$15") (pin "C") (pinfunction "P$1_C") (pintype "bidirectional"))
      (node (ref "U$16") (pin "C") (pinfunction "P$1_C") (pintype "bidirectional"))
      (node (ref "U$17") (pin "C") (pinfunction "P$1_C") (pintype "bidirectional"))
    )
    (net (code "43") (name "/KS3") (class "Default")
      (node (ref "IC1") (pin "4") (pinfunction "RA3/MCLR#/VPP_4") (pintype "input"))
      (node (ref "ICSP") (pin "1") (pinfunction "VPP/MCLR_1") (pintype "passive"))
      (node (ref "U$18") (pin "C") (pinfunction "P$1_C") (pintype "bidirectional"))
      (node (ref "U$19") (pin "C") (pinfunction "P$1_C") (pintype "bidirectional"))
      (node (ref "U$20") (pin "C") (pinfunction "P$1_C") (pintype "bidirectional"))
      (node (ref "U$21") (pin "C") (pinfunction "P$1_C") (pintype "bidirectional"))
      (node (ref "U$22") (pin "C") (pinfunction "P$1_C") (pintype "bidirectional"))
      (node (ref "U$23") (pin "C") (pinfunction "P$1_C") (pintype "bidirectional"))
      (node (ref "U$24") (pin "C") (pinfunction "P$1_C") (pintype "bidirectional"))
    )
    (net (code "44") (name "/SCL") (class "Default")
      (node (ref "IC1") (pin "10") (pinfunction "RCO/SCL/SCK_10") (pintype "bidirectional"))
      (node (ref "SCL") (pin "1") (pinfunction "1_1") (pintype "passive"))
    )
    (net (code "45") (name "/SDA") (class "Default")
      (node (ref "IC1") (pin "9") (pinfunction "RC1/SDA/SDI_9") (pintype "bidirectional"))
      (node (ref "SDA") (pin "1") (pinfunction "1_1") (pintype "passive"))
    )
    (net (code "46") (name "GND") (class "Default")
      (node (ref "C1") (pin "2") (pinfunction "2_2") (pintype "passive"))
      (node (ref "C2") (pin "2") (pinfunction "2_2") (pintype "passive"))
      (node (ref "C3") (pin "2") (pinfunction "2_2") (pintype "passive"))
      (node (ref "C4") (pin "2") (pinfunction "2_2") (pintype "passive"))
      (node (ref "C5") (pin "2") (pinfunction "2_2") (pintype "passive"))
      (node (ref "C6") (pin "-") (pinfunction "-_-") (pintype "passive"))
      (node (ref "GND") (pin "1") (pinfunction "1_1") (pintype "passive"))
      (node (ref "GND10") (pin "1") (pinfunction "1_1") (pintype "passive"))
      (node (ref "GND7") (pin "1") (pinfunction "1_1") (pintype "passive"))
      (node (ref "GND8") (pin "1") (pinfunction "1_1") (pintype "passive"))
      (node (ref "GND9") (pin "1") (pinfunction "1_1") (pintype "passive"))
      (node (ref "IC1") (pin "14") (pinfunction "VSS_14") (pintype "power_in"))
      (node (ref "IC2") (pin "13") (pinfunction "G_13") (pintype "input"))
      (node (ref "IC2") (pin "8") (pinfunction "GND_8") (pintype "power_in"))
      (node (ref "IC3") (pin "13") (pinfunction "G_13") (pintype "input"))
      (node (ref "IC3") (pin "8") (pinfunction "GND_8") (pintype "power_in"))
      (node (ref "IC4") (pin "16") (pinfunction "GND_16") (pintype "power_in"))
      (node (ref "IC5") (pin "13") (pinfunction "G_13") (pintype "input"))
      (node (ref "IC5") (pin "8") (pinfunction "GND_8") (pintype "power_in"))
      (node (ref "ICSP") (pin "3") (pinfunction "VSS(GND)_3") (pintype "power_in"))
    )
    (net (code "47") (name "Net-(DISP1-ROW1+)") (class "Default")
      (node (ref "DISP1") (pin "P$22") (pinfunction "ROW1+_P$22") (pintype "bidirectional"))
      (node (ref "R12") (pin "1") (pinfunction "1_1") (pintype "passive"))
    )
    (net (code "48") (name "Net-(DISP1-ROW2+)") (class "Default")
      (node (ref "DISP1") (pin "P$19") (pinfunction "ROW2+_P$19") (pintype "bidirectional"))
      (node (ref "R11") (pin "1") (pinfunction "1_1") (pintype "passive"))
    )
    (net (code "49") (name "Net-(DISP1-ROW3+)") (class "Default")
      (node (ref "DISP1") (pin "P$16") (pinfunction "ROW3+_P$16") (pintype "bidirectional"))
      (node (ref "R10") (pin "1") (pinfunction "1_1") (pintype "passive"))
    )
    (net (code "50") (name "Net-(DISP1-ROW4+)") (class "Default")
      (node (ref "DISP1") (pin "P$13") (pinfunction "ROW4+_P$13") (pintype "bidirectional"))
      (node (ref "R9") (pin "1") (pinfunction "1_1") (pintype "passive"))
    )
    (net (code "51") (name "Net-(DISP1-ROW5+)") (class "Default")
      (node (ref "DISP1") (pin "P$3") (pinfunction "ROW5+_P$3") (pintype "bidirectional"))
      (node (ref "R24") (pin "2") (pinfunction "2_2") (pintype "passive"))
    )
    (net (code "52") (name "Net-(DISP1-ROW6+)") (class "Default")
      (node (ref "DISP1") (pin "P$6") (pinfunction "ROW6+_P$6") (pintype "bidirectional"))
      (node (ref "R23") (pin "2") (pinfunction "2_2") (pintype "passive"))
    )
    (net (code "53") (name "Net-(DISP1-ROW7+)") (class "Default")
      (node (ref "DISP1") (pin "P$9") (pinfunction "ROW7+_P$9") (pintype "bidirectional"))
      (node (ref "R22") (pin "2") (pinfunction "2_2") (pintype "passive"))
    )
    (net (code "54") (name "Net-(DISP1-ROW8+)") (class "Default")
      (node (ref "DISP1") (pin "P$12") (pinfunction "ROW8+_P$12") (pintype "bidirectional"))
      (node (ref "R21") (pin "2") (pinfunction "2_2") (pintype "passive"))
    )
    (net (code "55") (name "Net-(DISP2-ROW1+)") (class "Default")
      (node (ref "DISP2") (pin "P$22") (pinfunction "ROW1+_P$22") (pintype "bidirectional"))
      (node (ref "R8") (pin "1") (pinfunction "1_1") (pintype "passive"))
    )
    (net (code "56") (name "Net-(DISP2-ROW2+)") (class "Default")
      (node (ref "DISP2") (pin "P$19") (pinfunction "ROW2+_P$19") (pintype "bidirectional"))
      (node (ref "R7") (pin "1") (pinfunction "1_1") (pintype "passive"))
    )
    (net (code "57") (name "Net-(DISP2-ROW3+)") (class "Default")
      (node (ref "DISP2") (pin "P$16") (pinfunction "ROW3+_P$16") (pintype "bidirectional"))
      (node (ref "R6") (pin "1") (pinfunction "1_1") (pintype "passive"))
    )
    (net (code "58") (name "Net-(DISP2-ROW4+)") (class "Default")
      (node (ref "DISP2") (pin "P$13") (pinfunction "ROW4+_P$13") (pintype "bidirectional"))
      (node (ref "R5") (pin "1") (pinfunction "1_1") (pintype "passive"))
    )
    (net (code "59") (name "Net-(DISP2-ROW5+)") (class "Default")
      (node (ref "DISP2") (pin "P$3") (pinfunction "ROW5+_P$3") (pintype "bidirectional"))
      (node (ref "R20") (pin "2") (pinfunction "2_2") (pintype "passive"))
    )
    (net (code "60") (name "Net-(DISP2-ROW6+)") (class "Default")
      (node (ref "DISP2") (pin "P$6") (pinfunction "ROW6+_P$6") (pintype "bidirectional"))
      (node (ref "R19") (pin "2") (pinfunction "2_2") (pintype "passive"))
    )
    (net (code "61") (name "Net-(DISP2-ROW7+)") (class "Default")
      (node (ref "DISP2") (pin "P$9") (pinfunction "ROW7+_P$9") (pintype "bidirectional"))
      (node (ref "R18") (pin "2") (pinfunction "2_2") (pintype "passive"))
    )
    (net (code "62") (name "Net-(DISP2-ROW8+)") (class "Default")
      (node (ref "DISP2") (pin "P$12") (pinfunction "ROW8+_P$12") (pintype "bidirectional"))
      (node (ref "R17") (pin "2") (pinfunction "2_2") (pintype "passive"))
    )
    (net (code "63") (name "Net-(DISP3-ROW1+)") (class "Default")
      (node (ref "DISP3") (pin "P$22") (pinfunction "ROW1+_P$22") (pintype "bidirectional"))
      (node (ref "R4") (pin "1") (pinfunction "1_1") (pintype "passive"))
    )
    (net (code "64") (name "Net-(DISP3-ROW2+)") (class "Default")
      (node (ref "DISP3") (pin "P$19") (pinfunction "ROW2+_P$19") (pintype "bidirectional"))
      (node (ref "R3") (pin "1") (pinfunction "1_1") (pintype "passive"))
    )
    (net (code "65") (name "Net-(DISP3-ROW3+)") (class "Default")
      (node (ref "DISP3") (pin "P$16") (pinfunction "ROW3+_P$16") (pintype "bidirectional"))
      (node (ref "R2") (pin "1") (pinfunction "1_1") (pintype "passive"))
    )
    (net (code "66") (name "Net-(DISP3-ROW4+)") (class "Default")
      (node (ref "DISP3") (pin "P$13") (pinfunction "ROW4+_P$13") (pintype "bidirectional"))
      (node (ref "R1") (pin "1") (pinfunction "1_1") (pintype "passive"))
    )
    (net (code "67") (name "Net-(DISP3-ROW5+)") (class "Default")
      (node (ref "DISP3") (pin "P$3") (pinfunction "ROW5+_P$3") (pintype "bidirectional"))
      (node (ref "R16") (pin "2") (pinfunction "2_2") (pintype "passive"))
    )
    (net (code "68") (name "Net-(DISP3-ROW6+)") (class "Default")
      (node (ref "DISP3") (pin "P$6") (pinfunction "ROW6+_P$6") (pintype "bidirectional"))
      (node (ref "R15") (pin "2") (pinfunction "2_2") (pintype "passive"))
    )
    (net (code "69") (name "Net-(DISP3-ROW7+)") (class "Default")
      (node (ref "DISP3") (pin "P$9") (pinfunction "ROW7+_P$9") (pintype "bidirectional"))
      (node (ref "R14") (pin "2") (pinfunction "2_2") (pintype "passive"))
    )
    (net (code "70") (name "Net-(DISP3-ROW8+)") (class "Default")
      (node (ref "DISP3") (pin "P$12") (pinfunction "ROW8+_P$12") (pintype "bidirectional"))
      (node (ref "R13") (pin "2") (pinfunction "2_2") (pintype "passive"))
    )
    (net (code "71") (name "Net-(E1-Pad1)") (class "Default")
      (node (ref "E1") (pin "1") (pinfunction "1_1") (pintype "passive"))
      (node (ref "ENC1") (pin "C") (pinfunction "C_C") (pintype "bidirectional"))
    )
    (net (code "72") (name "Net-(E2-Pad1)") (class "Default")
      (node (ref "E2") (pin "1") (pinfunction "1_1") (pintype "passive"))
      (node (ref "ENC1") (pin "B") (pinfunction "B_B") (pintype "bidirectional"))
    )
    (net (code "73") (name "Net-(E3-Pad1)") (class "Default")
      (node (ref "E3") (pin "1") (pinfunction "1_1") (pintype "passive"))
      (node (ref "ENC1") (pin "A") (pinfunction "A_A") (pintype "bidirectional"))
    )
    (net (code "74") (name "Net-(IC2A-QH*)") (class "Default")
      (node (ref "F") (pin "1") (pinfunction "1_1") (pintype "passive"))
      (node (ref "IC2") (pin "9") (pinfunction "QH*_9") (pintype "tri_state"))
    )
    (net (code "75") (name "Net-(IC3A-QH*)") (class "Default")
      (node (ref "I") (pin "1") (pinfunction "1_1") (pintype "passive"))
      (node (ref "IC3") (pin "9") (pinfunction "QH*_9") (pintype "tri_state"))
    )
    (net (code "76") (name "Net-(IC5A-QH*)") (class "Default")
      (node (ref "IC5") (pin "9") (pinfunction "QH*_9") (pintype "tri_state"))
      (node (ref "K") (pin "1") (pinfunction "1_1") (pintype "passive"))
    )
    (net (code "77") (name "Net-(SW1-S)") (class "Default")
      (node (ref "SW1") (pin "1") (pinfunction "S_1") (pintype "passive"))
      (node (ref "SW1") (pin "2") (pinfunction "S1_2") (pintype "passive"))
      (node (ref "U$2") (pin "A") (pinfunction "P$2_A") (pintype "bidirectional"))
    )
    (net (code "78") (name "Net-(SW2-S)") (class "Default")
      (node (ref "SW2") (pin "1") (pinfunction "S_1") (pintype "passive"))
      (node (ref "SW2") (pin "2") (pinfunction "S1_2") (pintype "passive"))
      (node (ref "U$5") (pin "A") (pinfunction "P$2_A") (pintype "bidirectional"))
    )
    (net (code "79") (name "Net-(SW3-S)") (class "Default")
      (node (ref "SW3") (pin "1") (pinfunction "S_1") (pintype "passive"))
      (node (ref "SW3") (pin "2") (pinfunction "S1_2") (pintype "passive"))
      (node (ref "U$3") (pin "A") (pinfunction "P$2_A") (pintype "bidirectional"))
    )
    (net (code "80") (name "Net-(SW4-S)") (class "Default")
      (node (ref "SW4") (pin "1") (pinfunction "S_1") (pintype "passive"))
      (node (ref "SW4") (pin "2") (pinfunction "S1_2") (pintype "passive"))
      (node (ref "U$4") (pin "A") (pinfunction "P$2_A") (pintype "bidirectional"))
    )
    (net (code "81") (name "Net-(SW5-S)") (class "Default")
      (node (ref "SW5") (pin "1") (pinfunction "S_1") (pintype "passive"))
      (node (ref "SW5") (pin "2") (pinfunction "S1_2") (pintype "passive"))
      (node (ref "U$12") (pin "A") (pinfunction "P$2_A") (pintype "bidirectional"))
    )
    (net (code "82") (name "Net-(SW6-S)") (class "Default")
      (node (ref "SW6") (pin "1") (pinfunction "S_1") (pintype "passive"))
      (node (ref "SW6") (pin "2") (pinfunction "S1_2") (pintype "passive"))
      (node (ref "U$14") (pin "A") (pinfunction "P$2_A") (pintype "bidirectional"))
    )
    (net (code "83") (name "Net-(SW7-S)") (class "Default")
      (node (ref "SW7") (pin "1") (pinfunction "S_1") (pintype "passive"))
      (node (ref "SW7") (pin "2") (pinfunction "S1_2") (pintype "passive"))
      (node (ref "U$6") (pin "A") (pinfunction "P$2_A") (pintype "bidirectional"))
    )
    (net (code "84") (name "Net-(SW8-S)") (class "Default")
      (node (ref "SW8") (pin "1") (pinfunction "S_1") (pintype "passive"))
      (node (ref "SW8") (pin "2") (pinfunction "S1_2") (pintype "passive"))
      (node (ref "U$15") (pin "A") (pinfunction "P$2_A") (pintype "bidirectional"))
    )
    (net (code "85") (name "Net-(SW9-S)") (class "Default")
      (node (ref "SW9") (pin "1") (pinfunction "S_1") (pintype "passive"))
      (node (ref "SW9") (pin "2") (pinfunction "S1_2") (pintype "passive"))
      (node (ref "U$8") (pin "A") (pinfunction "P$2_A") (pintype "bidirectional"))
    )
    (net (code "86") (name "Net-(SW10-S)") (class "Default")
      (node (ref "SW10") (pin "1") (pinfunction "S_1") (pintype "passive"))
      (node (ref "SW10") (pin "2") (pinfunction "S1_2") (pintype "passive"))
      (node (ref "U$16") (pin "A") (pinfunction "P$2_A") (pintype "bidirectional"))
    )
    (net (code "87") (name "Net-(SW11-S)") (class "Default")
      (node (ref "SW11") (pin "1") (pinfunction "S_1") (pintype "passive"))
      (node (ref "SW11") (pin "2") (pinfunction "S1_2") (pintype "passive"))
      (node (ref "U$9") (pin "A") (pinfunction "P$2_A") (pintype "bidirectional"))
    )
    (net (code "88") (name "Net-(SW12-S)") (class "Default")
      (node (ref "SW12") (pin "1") (pinfunction "S_1") (pintype "passive"))
      (node (ref "SW12") (pin "2") (pinfunction "S1_2") (pintype "passive"))
      (node (ref "U$17") (pin "A") (pinfunction "P$2_A") (pintype "bidirectional"))
    )
    (net (code "89") (name "Net-(SW13-S)") (class "Default")
      (node (ref "SW13") (pin "1") (pinfunction "S_1") (pintype "passive"))
      (node (ref "SW13") (pin "2") (pinfunction "S1_2") (pintype "passive"))
      (node (ref "U$7") (pin "A") (pinfunction "P$2_A") (pintype "bidirectional"))
    )
    (net (code "90") (name "Net-(SW14-S)") (class "Default")
      (node (ref "SW14") (pin "1") (pinfunction "S_1") (pintype "passive"))
      (node (ref "SW14") (pin "2") (pinfunction "S1_2") (pintype "passive"))
      (node (ref "U$10") (pin "A") (pinfunction "P$2_A") (pintype "bidirectional"))
    )
    (net (code "91") (name "Net-(SW15-S)") (class "Default")
      (node (ref "SW15") (pin "1") (pinfunction "S_1") (pintype "passive"))
      (node (ref "SW15") (pin "2") (pinfunction "S1_2") (pintype "passive"))
      (node (ref "U$11") (pin "A") (pinfunction "P$2_A") (pintype "bidirectional"))
    )
    (net (code "92") (name "Net-(SW16-S)") (class "Default")
      (node (ref "SW16") (pin "1") (pinfunction "S_1") (pintype "passive"))
      (node (ref "SW16") (pin "2") (pinfunction "S1_2") (pintype "passive"))
      (node (ref "U$13") (pin "A") (pinfunction "P$2_A") (pintype "bidirectional"))
    )
    (net (code "93") (name "Net-(SW17-S)") (class "Default")
      (node (ref "SW17") (pin "1") (pinfunction "S_1") (pintype "passive"))
      (node (ref "SW17") (pin "2") (pinfunction "S1_2") (pintype "passive"))
      (node (ref "U$22") (pin "A") (pinfunction "P$2_A") (pintype "bidirectional"))
    )
    (net (code "94") (name "Net-(SW18-S)") (class "Default")
      (node (ref "SW18") (pin "1") (pinfunction "S_1") (pintype "passive"))
      (node (ref "SW18") (pin "2") (pinfunction "S1_2") (pintype "passive"))
      (node (ref "U$24") (pin "A") (pinfunction "P$2_A") (pintype "bidirectional"))
    )
    (net (code "95") (name "Net-(SW19-S)") (class "Default")
      (node (ref "SW19") (pin "1") (pinfunction "S_1") (pintype "passive"))
      (node (ref "SW19") (pin "2") (pinfunction "S1_2") (pintype "passive"))
      (node (ref "U$18") (pin "A") (pinfunction "P$2_A") (pintype "bidirectional"))
    )
    (net (code "96") (name "Net-(SW20-S)") (class "Default")
      (node (ref "SW20") (pin "1") (pinfunction "S_1") (pintype "passive"))
      (node (ref "SW20") (pin "2") (pinfunction "S1_2") (pintype "passive"))
      (node (ref "U$19") (pin "A") (pinfunction "P$2_A") (pintype "bidirectional"))
    )
    (net (code "97") (name "Net-(SW21-S)") (class "Default")
      (node (ref "SW21") (pin "1") (pinfunction "S_1") (pintype "passive"))
      (node (ref "SW21") (pin "2") (pinfunction "S1_2") (pintype "passive"))
      (node (ref "U$20") (pin "A") (pinfunction "P$2_A") (pintype "bidirectional"))
    )
    (net (code "98") (name "Net-(SW22-S)") (class "Default")
      (node (ref "SW22") (pin "1") (pinfunction "S_1") (pintype "passive"))
      (node (ref "SW22") (pin "2") (pinfunction "S1_2") (pintype "passive"))
      (node (ref "U$21") (pin "A") (pinfunction "P$2_A") (pintype "bidirectional"))
    )
    (net (code "99") (name "Net-(SW23-S)") (class "Default")
      (node (ref "SW23") (pin "1") (pinfunction "S_1") (pintype "passive"))
      (node (ref "SW23") (pin "2") (pinfunction "S1_2") (pintype "passive"))
      (node (ref "U$23") (pin "A") (pinfunction "P$2_A") (pintype "bidirectional"))
    )
    (net (code "100") (name "unconnected-(IC4-Q7S-Pad9)") (class "Default")
      (node (ref "IC4") (pin "9") (pinfunction "Q7S_9") (pintype "output"))
    )
    (net (code "101") (name "unconnected-(ICSP-LVP-Pad6)") (class "Default")
      (node (ref "ICSP") (pin "6") (pinfunction "LVP_6") (pintype "bidirectional"))
    )
    (net (code "102") (name "unconnected-(NC-Pad1)") (class "Default")
      (node (ref "NC") (pin "1") (pinfunction "1_1") (pintype "passive"))
    )
  )
)
